# gateway.net
KiCad netlist of a schematic drawn in EAGLE
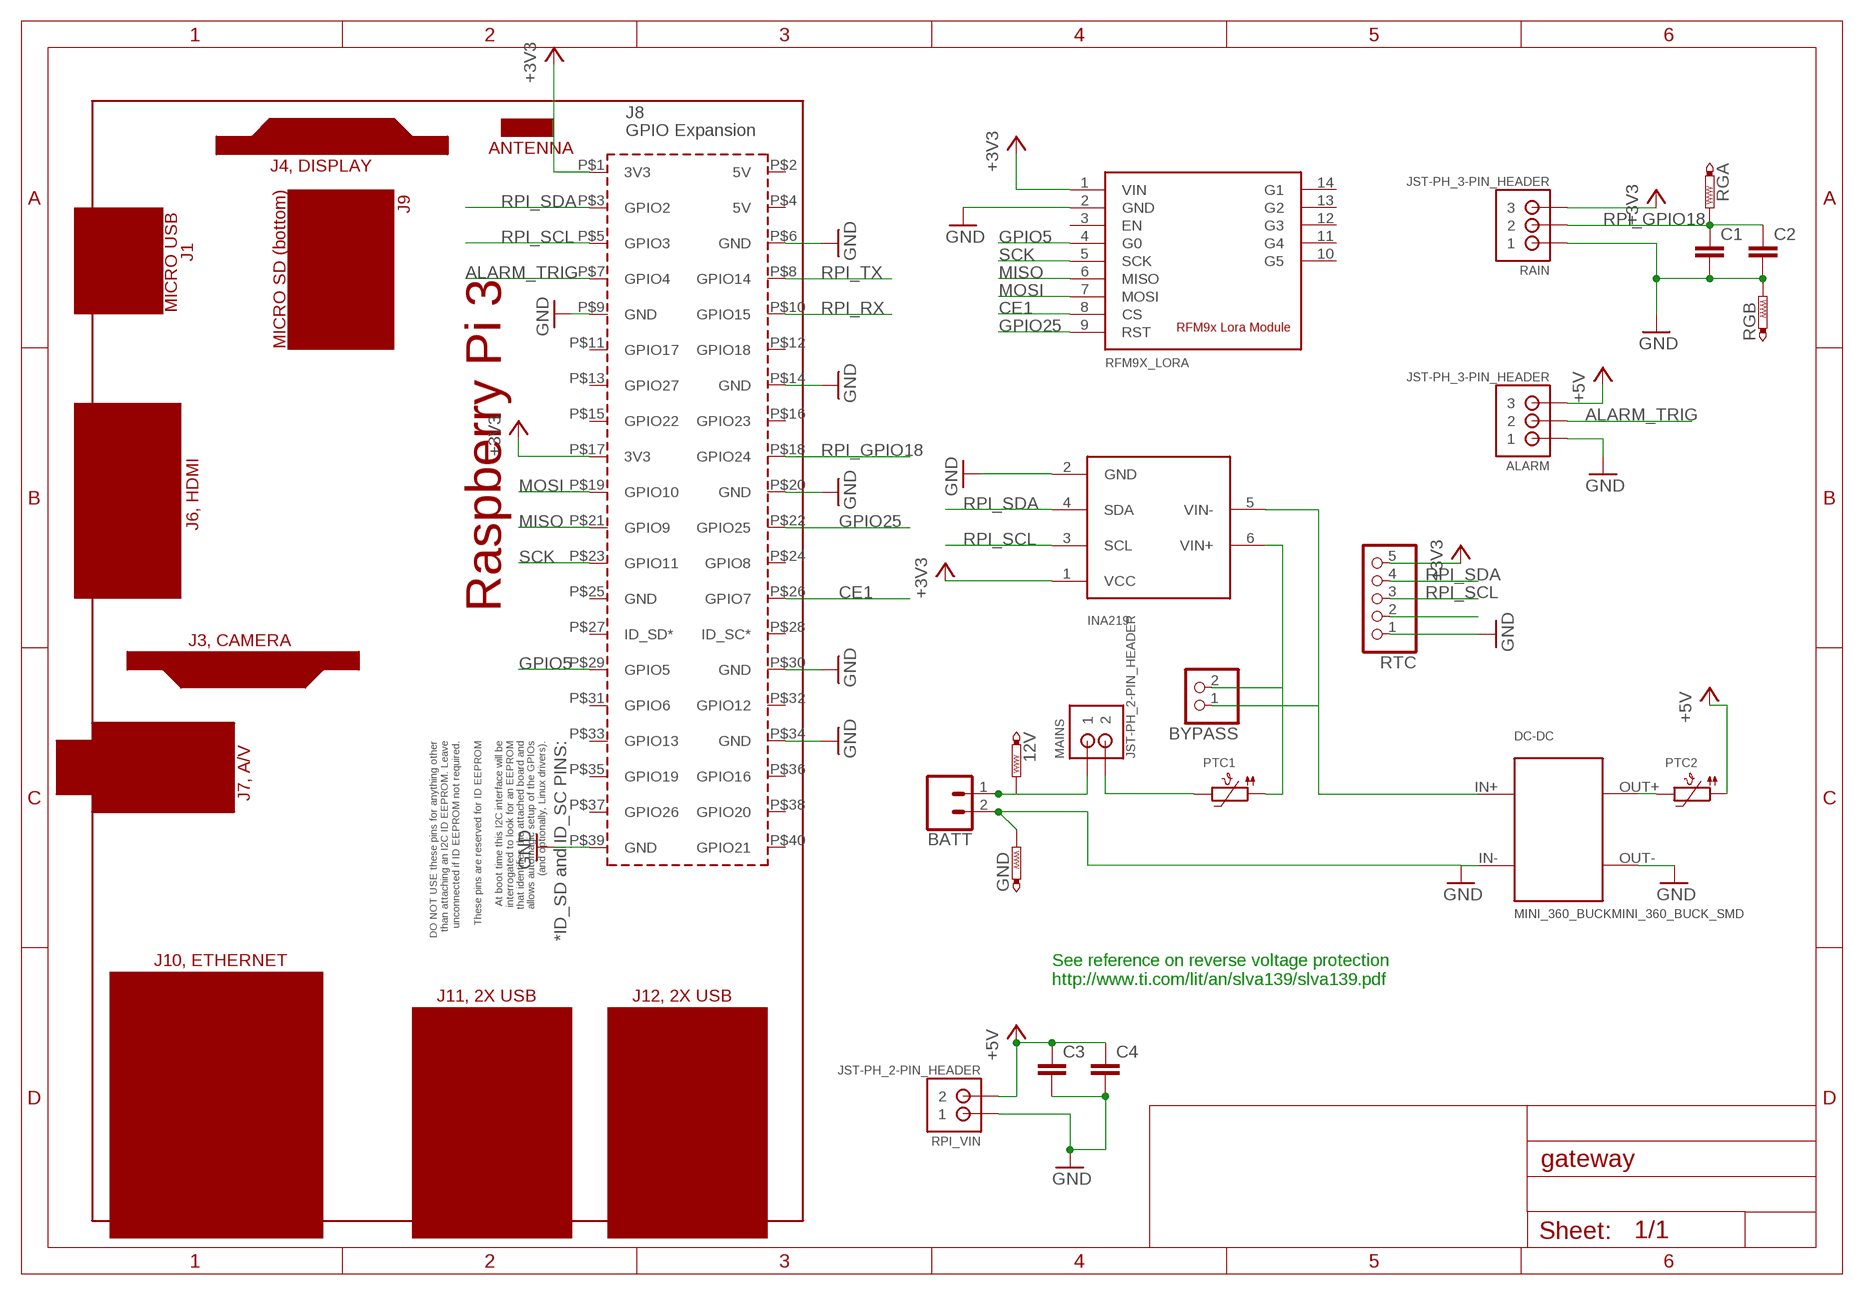
[diagram p0: schematic, sheet 1]

(export (version "E")
  (design (tool "Eeschema 10.0.6"))
  (components
    (comp (ref "12V")
      (value "PTR1PAD1-13")
      (footprint "eagle-import:P1-13")
      (libsource (lib "eagle-import") (part "PTR1PAD1-13"))
    )
    (comp (ref "ALARM")
      (value "JST-PH_3-PIN_HEADER")
      (footprint "eagle-import:JST_B3B-PH_HEADER")
      (libsource (lib "eagle-import") (part "JST-PH_3-PIN_HEADER"))
    )
    (comp (ref "BATT")
      (value "CONN_02POLAR")
      (footprint "eagle-import:MOLEX-1X2")
      (libsource (lib "eagle-import") (part "CONN_02POLAR"))
    )
    (comp (ref "BYPASS")
      (value "PINHD-1X2")
      (footprint "eagle-import:1X02")
      (libsource (lib "eagle-import") (part "PINHD-1X2"))
    )
    (comp (ref "C1")
      (value "C-EUC0805")
      (footprint "eagle-import:C0805")
      (libsource (lib "eagle-import") (part "C-EUC0805"))
    )
    (comp (ref "C2")
      (value "C-EUC0805")
      (footprint "eagle-import:C0805")
      (libsource (lib "eagle-import") (part "C-EUC0805"))
    )
    (comp (ref "C3")
      (value "C-EUC1210")
      (footprint "eagle-import:C1210")
      (libsource (lib "eagle-import") (part "C-EUC1210"))
    )
    (comp (ref "C4")
      (value "C-EUC2012")
      (footprint "eagle-import:C2012")
      (libsource (lib "eagle-import") (part "C-EUC2012"))
    )
    (comp (ref "DC-DC")
      (value "MINI_360_BUCKMINI_360_BUCK_SMD")
      (footprint "eagle-import:MINI_360_BUCK_SMD")
      (libsource (lib "eagle-import") (part "MINI_360_BUCKMINI_360_BUCK_SMD"))
    )
    (comp (ref "GND")
      (value "PTR1PAD1-13")
      (footprint "eagle-import:P1-13")
      (libsource (lib "eagle-import") (part "PTR1PAD1-13"))
    )
    (comp (ref "INA219")
      (value "INA219")
      (footprint "eagle-import:INA219")
      (libsource (lib "eagle-import") (part "INA219"))
    )
    (comp (ref "MAINS")
      (value "JST-PH_2-PIN_HEADER")
      (footprint "eagle-import:JST_B2B-PH_HEADER")
      (libsource (lib "eagle-import") (part "JST-PH_2-PIN_HEADER"))
    )
    (comp (ref "PCB2")
      (value "RPI3")
      (footprint "eagle-import:RPI3")
      (libsource (lib "eagle-import") (part "RPI3"))
    )
    (comp (ref "PTC1")
      (value "PTC1206")
      (footprint "eagle-import:1206")
      (libsource (lib "eagle-import") (part "PTC1206"))
    )
    (comp (ref "PTC2")
      (value "PTC1210")
      (footprint "eagle-import:PTC1210")
      (libsource (lib "eagle-import") (part "PTC1210"))
    )
    (comp (ref "RAIN")
      (value "JST-PH_3-PIN_HEADER")
      (footprint "eagle-import:JST_B3B-PH_HEADER")
      (libsource (lib "eagle-import") (part "JST-PH_3-PIN_HEADER"))
    )
    (comp (ref "RFM9X_LORA")
      (value "RFM9X_MODULE")
      (footprint "eagle-import:RFM9X_MODULE")
      (libsource (lib "eagle-import") (part "RFM9X_MODULE"))
    )
    (comp (ref "RGA")
      (value "PTR1PAD1-13")
      (footprint "eagle-import:P1-13")
      (libsource (lib "eagle-import") (part "PTR1PAD1-13"))
    )
    (comp (ref "RGB")
      (value "PTR1PAD1-13")
      (footprint "eagle-import:P1-13")
      (libsource (lib "eagle-import") (part "PTR1PAD1-13"))
    )
    (comp (ref "RPI_VIN")
      (value "JST-PH_2-PIN_HEADER")
      (footprint "eagle-import:JST_B2B-PH_HEADER")
      (libsource (lib "eagle-import") (part "JST-PH_2-PIN_HEADER"))
    )
    (comp (ref "RTC")
      (value "PINHD-1X5")
      (footprint "eagle-import:1X05")
      (libsource (lib "eagle-import") (part "PINHD-1X5"))
    )
  )
  (nets
    (net (code "1") (name "+3V3") (class "Default")
      (node (ref "INA219") (pin "1") (pinfunction "VCC_1") (pintype "bidirectional"))
      (node (ref "PCB2") (pin "P$1") (pinfunction "3V3_P$1") (pintype "bidirectional"))
      (node (ref "PCB2") (pin "P$17") (pinfunction "3V3_P$17") (pintype "bidirectional"))
      (node (ref "RAIN") (pin "P3") (pinfunction "3_P3") (pintype "bidirectional"))
      (node (ref "RFM9X_LORA") (pin "1") (pinfunction "VIN_1") (pintype "bidirectional"))
      (node (ref "RTC") (pin "5") (pinfunction "5_5") (pintype "passive"))
    )
    (net (code "2") (name "+5V") (class "Default")
      (node (ref "ALARM") (pin "P3") (pinfunction "3_P3") (pintype "bidirectional"))
      (node (ref "C3") (pin "1") (pinfunction "1_1") (pintype "passive"))
      (node (ref "C4") (pin "1") (pinfunction "1_1") (pintype "passive"))
      (node (ref "PTC2") (pin "P$1") (pinfunction "1_P$1") (pintype "passive"))
      (node (ref "RPI_VIN") (pin "P2") (pinfunction "2_P2") (pintype "bidirectional"))
    )
    (net (code "3") (name "/ALARM_TRIG") (class "Default")
      (node (ref "ALARM") (pin "P2") (pinfunction "2_P2") (pintype "bidirectional"))
      (node (ref "PCB2") (pin "P$7") (pinfunction "GPIO4_P$7") (pintype "bidirectional"))
    )
    (net (code "4") (name "/CE1") (class "Default")
      (node (ref "PCB2") (pin "P$26") (pinfunction "GPIO7_P$26") (pintype "bidirectional"))
      (node (ref "RFM9X_LORA") (pin "8") (pinfunction "CS_8") (pintype "bidirectional"))
    )
    (net (code "5") (name "/GPIO5") (class "Default")
      (node (ref "PCB2") (pin "P$29") (pinfunction "GPIO5_P$29") (pintype "bidirectional"))
      (node (ref "RFM9X_LORA") (pin "4") (pinfunction "G0_4") (pintype "bidirectional"))
    )
    (net (code "6") (name "/GPIO25") (class "Default")
      (node (ref "PCB2") (pin "P$22") (pinfunction "GPIO25_P$22") (pintype "bidirectional"))
      (node (ref "RFM9X_LORA") (pin "9") (pinfunction "RST_9") (pintype "bidirectional"))
    )
    (net (code "7") (name "/MISO") (class "Default")
      (node (ref "PCB2") (pin "P$21") (pinfunction "GPIO9_P$21") (pintype "bidirectional"))
      (node (ref "RFM9X_LORA") (pin "6") (pinfunction "MISO_6") (pintype "bidirectional"))
    )
    (net (code "8") (name "/MOSI") (class "Default")
      (node (ref "PCB2") (pin "P$19") (pinfunction "GPIO10_P$19") (pintype "bidirectional"))
      (node (ref "RFM9X_LORA") (pin "7") (pinfunction "MOSI_7") (pintype "bidirectional"))
    )
    (net (code "9") (name "/RPI_GPIO18") (class "Default")
      (node (ref "C1") (pin "1") (pinfunction "1_1") (pintype "passive"))
      (node (ref "C2") (pin "1") (pinfunction "1_1") (pintype "passive"))
      (node (ref "PCB2") (pin "P$18") (pinfunction "GPIO24_P$18") (pintype "bidirectional"))
      (node (ref "RAIN") (pin "P2") (pinfunction "2_P2") (pintype "bidirectional"))
      (node (ref "RGA") (pin "TP") (pinfunction "TP_TP") (pintype "input"))
    )
    (net (code "10") (name "/RPI_RX") (class "Default")
      (node (ref "PCB2") (pin "P$10") (pinfunction "GPIO15_P$10") (pintype "bidirectional"))
    )
    (net (code "11") (name "/RPI_SCL") (class "Default")
      (node (ref "INA219") (pin "3") (pinfunction "SCL_3") (pintype "bidirectional"))
      (node (ref "PCB2") (pin "P$5") (pinfunction "GPIO3_P$5") (pintype "bidirectional"))
      (node (ref "RTC") (pin "3") (pinfunction "3_3") (pintype "passive"))
    )
    (net (code "12") (name "/RPI_SDA") (class "Default")
      (node (ref "INA219") (pin "4") (pinfunction "SDA_4") (pintype "bidirectional"))
      (node (ref "PCB2") (pin "P$3") (pinfunction "GPIO2_P$3") (pintype "bidirectional"))
      (node (ref "RTC") (pin "4") (pinfunction "4_4") (pintype "passive"))
    )
    (net (code "13") (name "/RPI_TX") (class "Default")
      (node (ref "PCB2") (pin "P$8") (pinfunction "GPIO14_P$8") (pintype "bidirectional"))
    )
    (net (code "14") (name "/SCK") (class "Default")
      (node (ref "PCB2") (pin "P$23") (pinfunction "GPIO11_P$23") (pintype "bidirectional"))
      (node (ref "RFM9X_LORA") (pin "5") (pinfunction "SCK_5") (pintype "bidirectional"))
    )
    (net (code "15") (name "GND") (class "Default")
      (node (ref "ALARM") (pin "P1") (pinfunction "1_P1") (pintype "bidirectional"))
      (node (ref "BATT") (pin "2") (pinfunction "2_2") (pintype "passive"))
      (node (ref "C1") (pin "2") (pinfunction "2_2") (pintype "passive"))
      (node (ref "C2") (pin "2") (pinfunction "2_2") (pintype "passive"))
      (node (ref "C3") (pin "2") (pinfunction "2_2") (pintype "passive"))
      (node (ref "C4") (pin "2") (pinfunction "2_2") (pintype "passive"))
      (node (ref "DC-DC") (pin "IN-") (pinfunction "VIN-_IN-") (pintype "power_in"))
      (node (ref "DC-DC") (pin "OUT-") (pinfunction "VOUT-_OUT-") (pintype "power_in"))
      (node (ref "GND") (pin "TP") (pinfunction "TP_TP") (pintype "input"))
      (node (ref "INA219") (pin "2") (pinfunction "GND_2") (pintype "bidirectional"))
      (node (ref "PCB2") (pin "P$14") (pinfunction "GND_P$14") (pintype "bidirectional"))
      (node (ref "PCB2") (pin "P$20") (pinfunction "GND_P$20") (pintype "bidirectional"))
      (node (ref "PCB2") (pin "P$30") (pinfunction "GND_P$30") (pintype "bidirectional"))
      (node (ref "PCB2") (pin "P$34") (pinfunction "GND_P$34") (pintype "bidirectional"))
      (node (ref "PCB2") (pin "P$39") (pinfunction "GND_P$39") (pintype "bidirectional"))
      (node (ref "PCB2") (pin "P$6") (pinfunction "GND_P$6") (pintype "bidirectional"))
      (node (ref "PCB2") (pin "P$9") (pinfunction "GND_P$9") (pintype "bidirectional"))
      (node (ref "RAIN") (pin "P1") (pinfunction "1_P1") (pintype "bidirectional"))
      (node (ref "RFM9X_LORA") (pin "2") (pinfunction "GND_2") (pintype "bidirectional"))
      (node (ref "RGB") (pin "TP") (pinfunction "TP_TP") (pintype "input"))
      (node (ref "RPI_VIN") (pin "P1") (pinfunction "1_P1") (pintype "bidirectional"))
      (node (ref "RTC") (pin "1") (pinfunction "1_1") (pintype "passive"))
    )
    (net (code "16") (name "Net-(DC-DC-VIN+)") (class "Default")
      (node (ref "BYPASS") (pin "1") (pinfunction "1_1") (pintype "passive"))
      (node (ref "DC-DC") (pin "IN+") (pinfunction "VIN+_IN+") (pintype "power_in"))
      (node (ref "INA219") (pin "5") (pinfunction "VIN-_5") (pintype "bidirectional"))
    )
    (net (code "17") (name "Net-(DC-DC-VOUT+)") (class "Default")
      (node (ref "DC-DC") (pin "OUT+") (pinfunction "VOUT+_OUT+") (pintype "power_in"))
      (node (ref "PTC2") (pin "P$2") (pinfunction "2_P$2") (pintype "passive"))
    )
    (net (code "18") (name "Net-(INA219-VIN+)") (class "Default")
      (node (ref "BYPASS") (pin "2") (pinfunction "2_2") (pintype "passive"))
      (node (ref "INA219") (pin "6") (pinfunction "VIN+_6") (pintype "bidirectional"))
      (node (ref "PTC1") (pin "1") (pinfunction "1_1") (pintype "passive"))
    )
    (net (code "19") (name "Net-(MAINS-1)") (class "Default")
      (node (ref "12V") (pin "TP") (pinfunction "TP_TP") (pintype "input"))
      (node (ref "BATT") (pin "1") (pinfunction "1_1") (pintype "passive"))
      (node (ref "MAINS") (pin "P1") (pinfunction "1_P1") (pintype "bidirectional"))
    )
    (net (code "20") (name "Net-(MAINS-2)") (class "Default")
      (node (ref "MAINS") (pin "P2") (pinfunction "2_P2") (pintype "bidirectional"))
      (node (ref "PTC1") (pin "2") (pinfunction "2_2") (pintype "passive"))
    )
    (net (code "21") (name "unconnected-(PCB2-5V-PadP$2)") (class "Default")
      (node (ref "PCB2") (pin "P$2") (pinfunction "5V_P$2") (pintype "bidirectional"))
    )
    (net (code "22") (name "unconnected-(PCB2-5V-PadP$4)") (class "Default")
      (node (ref "PCB2") (pin "P$4") (pinfunction "5V_P$4") (pintype "bidirectional"))
    )
    (net (code "23") (name "unconnected-(PCB2-GND-PadP$25)") (class "Default")
      (node (ref "PCB2") (pin "P$25") (pinfunction "GND_P$25") (pintype "bidirectional"))
    )
    (net (code "24") (name "unconnected-(PCB2-GPIO6-PadP$31)") (class "Default")
      (node (ref "PCB2") (pin "P$31") (pinfunction "GPIO6_P$31") (pintype "bidirectional"))
    )
    (net (code "25") (name "unconnected-(PCB2-GPIO8-PadP$24)") (class "Default")
      (node (ref "PCB2") (pin "P$24") (pinfunction "GPIO8_P$24") (pintype "bidirectional"))
    )
    (net (code "26") (name "unconnected-(PCB2-GPIO12-PadP$32)") (class "Default")
      (node (ref "PCB2") (pin "P$32") (pinfunction "GPIO12_P$32") (pintype "bidirectional"))
    )
    (net (code "27") (name "unconnected-(PCB2-GPIO13-PadP$33)") (class "Default")
      (node (ref "PCB2") (pin "P$33") (pinfunction "GPIO13_P$33") (pintype "bidirectional"))
    )
    (net (code "28") (name "unconnected-(PCB2-GPIO16-PadP$36)") (class "Default")
      (node (ref "PCB2") (pin "P$36") (pinfunction "GPIO16_P$36") (pintype "bidirectional"))
    )
    (net (code "29") (name "unconnected-(PCB2-GPIO17-PadP$11)") (class "Default")
      (node (ref "PCB2") (pin "P$11") (pinfunction "GPIO17_P$11") (pintype "bidirectional"))
    )
    (net (code "30") (name "unconnected-(PCB2-GPIO18-PadP$12)") (class "Default")
      (node (ref "PCB2") (pin "P$12") (pinfunction "GPIO18_P$12") (pintype "bidirectional"))
    )
    (net (code "31") (name "unconnected-(PCB2-GPIO19-PadP$35)") (class "Default")
      (node (ref "PCB2") (pin "P$35") (pinfunction "GPIO19_P$35") (pintype "bidirectional"))
    )
    (net (code "32") (name "unconnected-(PCB2-GPIO20-PadP$38)") (class "Default")
      (node (ref "PCB2") (pin "P$38") (pinfunction "GPIO20_P$38") (pintype "bidirectional"))
    )
    (net (code "33") (name "unconnected-(PCB2-GPIO21-PadP$40)") (class "Default")
      (node (ref "PCB2") (pin "P$40") (pinfunction "GPIO21_P$40") (pintype "bidirectional"))
    )
    (net (code "34") (name "unconnected-(PCB2-GPIO22-PadP$15)") (class "Default")
      (node (ref "PCB2") (pin "P$15") (pinfunction "GPIO22_P$15") (pintype "bidirectional"))
    )
    (net (code "35") (name "unconnected-(PCB2-GPIO23-PadP$16)") (class "Default")
      (node (ref "PCB2") (pin "P$16") (pinfunction "GPIO23_P$16") (pintype "bidirectional"))
    )
    (net (code "36") (name "unconnected-(PCB2-GPIO26-PadP$37)") (class "Default")
      (node (ref "PCB2") (pin "P$37") (pinfunction "GPIO26_P$37") (pintype "bidirectional"))
    )
    (net (code "37") (name "unconnected-(PCB2-GPIO27-PadP$13)") (class "Default")
      (node (ref "PCB2") (pin "P$13") (pinfunction "GPIO27_P$13") (pintype "bidirectional"))
    )
    (net (code "38") (name "unconnected-(PCB2-ID_SC*-PadP$28)") (class "Default")
      (node (ref "PCB2") (pin "P$28") (pinfunction "ID_SC*_P$28") (pintype "bidirectional"))
    )
    (net (code "39") (name "unconnected-(PCB2-ID_SD*-PadP$27)") (class "Default")
      (node (ref "PCB2") (pin "P$27") (pinfunction "ID_SD*_P$27") (pintype "bidirectional"))
    )
    (net (code "40") (name "unconnected-(RFM9X_LORA-EN-Pad3)") (class "Default")
      (node (ref "RFM9X_LORA") (pin "3") (pinfunction "EN_3") (pintype "bidirectional"))
    )
    (net (code "41") (name "unconnected-(RFM9X_LORA-G1-Pad14)") (class "Default")
      (node (ref "RFM9X_LORA") (pin "14") (pinfunction "G1_14") (pintype "bidirectional"))
    )
    (net (code "42") (name "unconnected-(RFM9X_LORA-G2-Pad13)") (class "Default")
      (node (ref "RFM9X_LORA") (pin "13") (pinfunction "G2_13") (pintype "bidirectional"))
    )
    (net (code "43") (name "unconnected-(RFM9X_LORA-G3-Pad12)") (class "Default")
      (node (ref "RFM9X_LORA") (pin "12") (pinfunction "G3_12") (pintype "bidirectional"))
    )
    (net (code "44") (name "unconnected-(RFM9X_LORA-G4-Pad11)") (class "Default")
      (node (ref "RFM9X_LORA") (pin "11") (pinfunction "G4_11") (pintype "bidirectional"))
    )
    (net (code "45") (name "unconnected-(RFM9X_LORA-G5-Pad10)") (class "Default")
      (node (ref "RFM9X_LORA") (pin "10") (pinfunction "G5_10") (pintype "bidirectional"))
    )
    (net (code "46") (name "unconnected-(RTC-Pad2)") (class "Default")
      (node (ref "RTC") (pin "2") (pinfunction "2_2") (pintype "passive"))
    )
  )
)
